# 2126_B_MatrixBoard_AffichageMatricielNom.net
KiCad netlist of a schematic drawn in Altium Designer
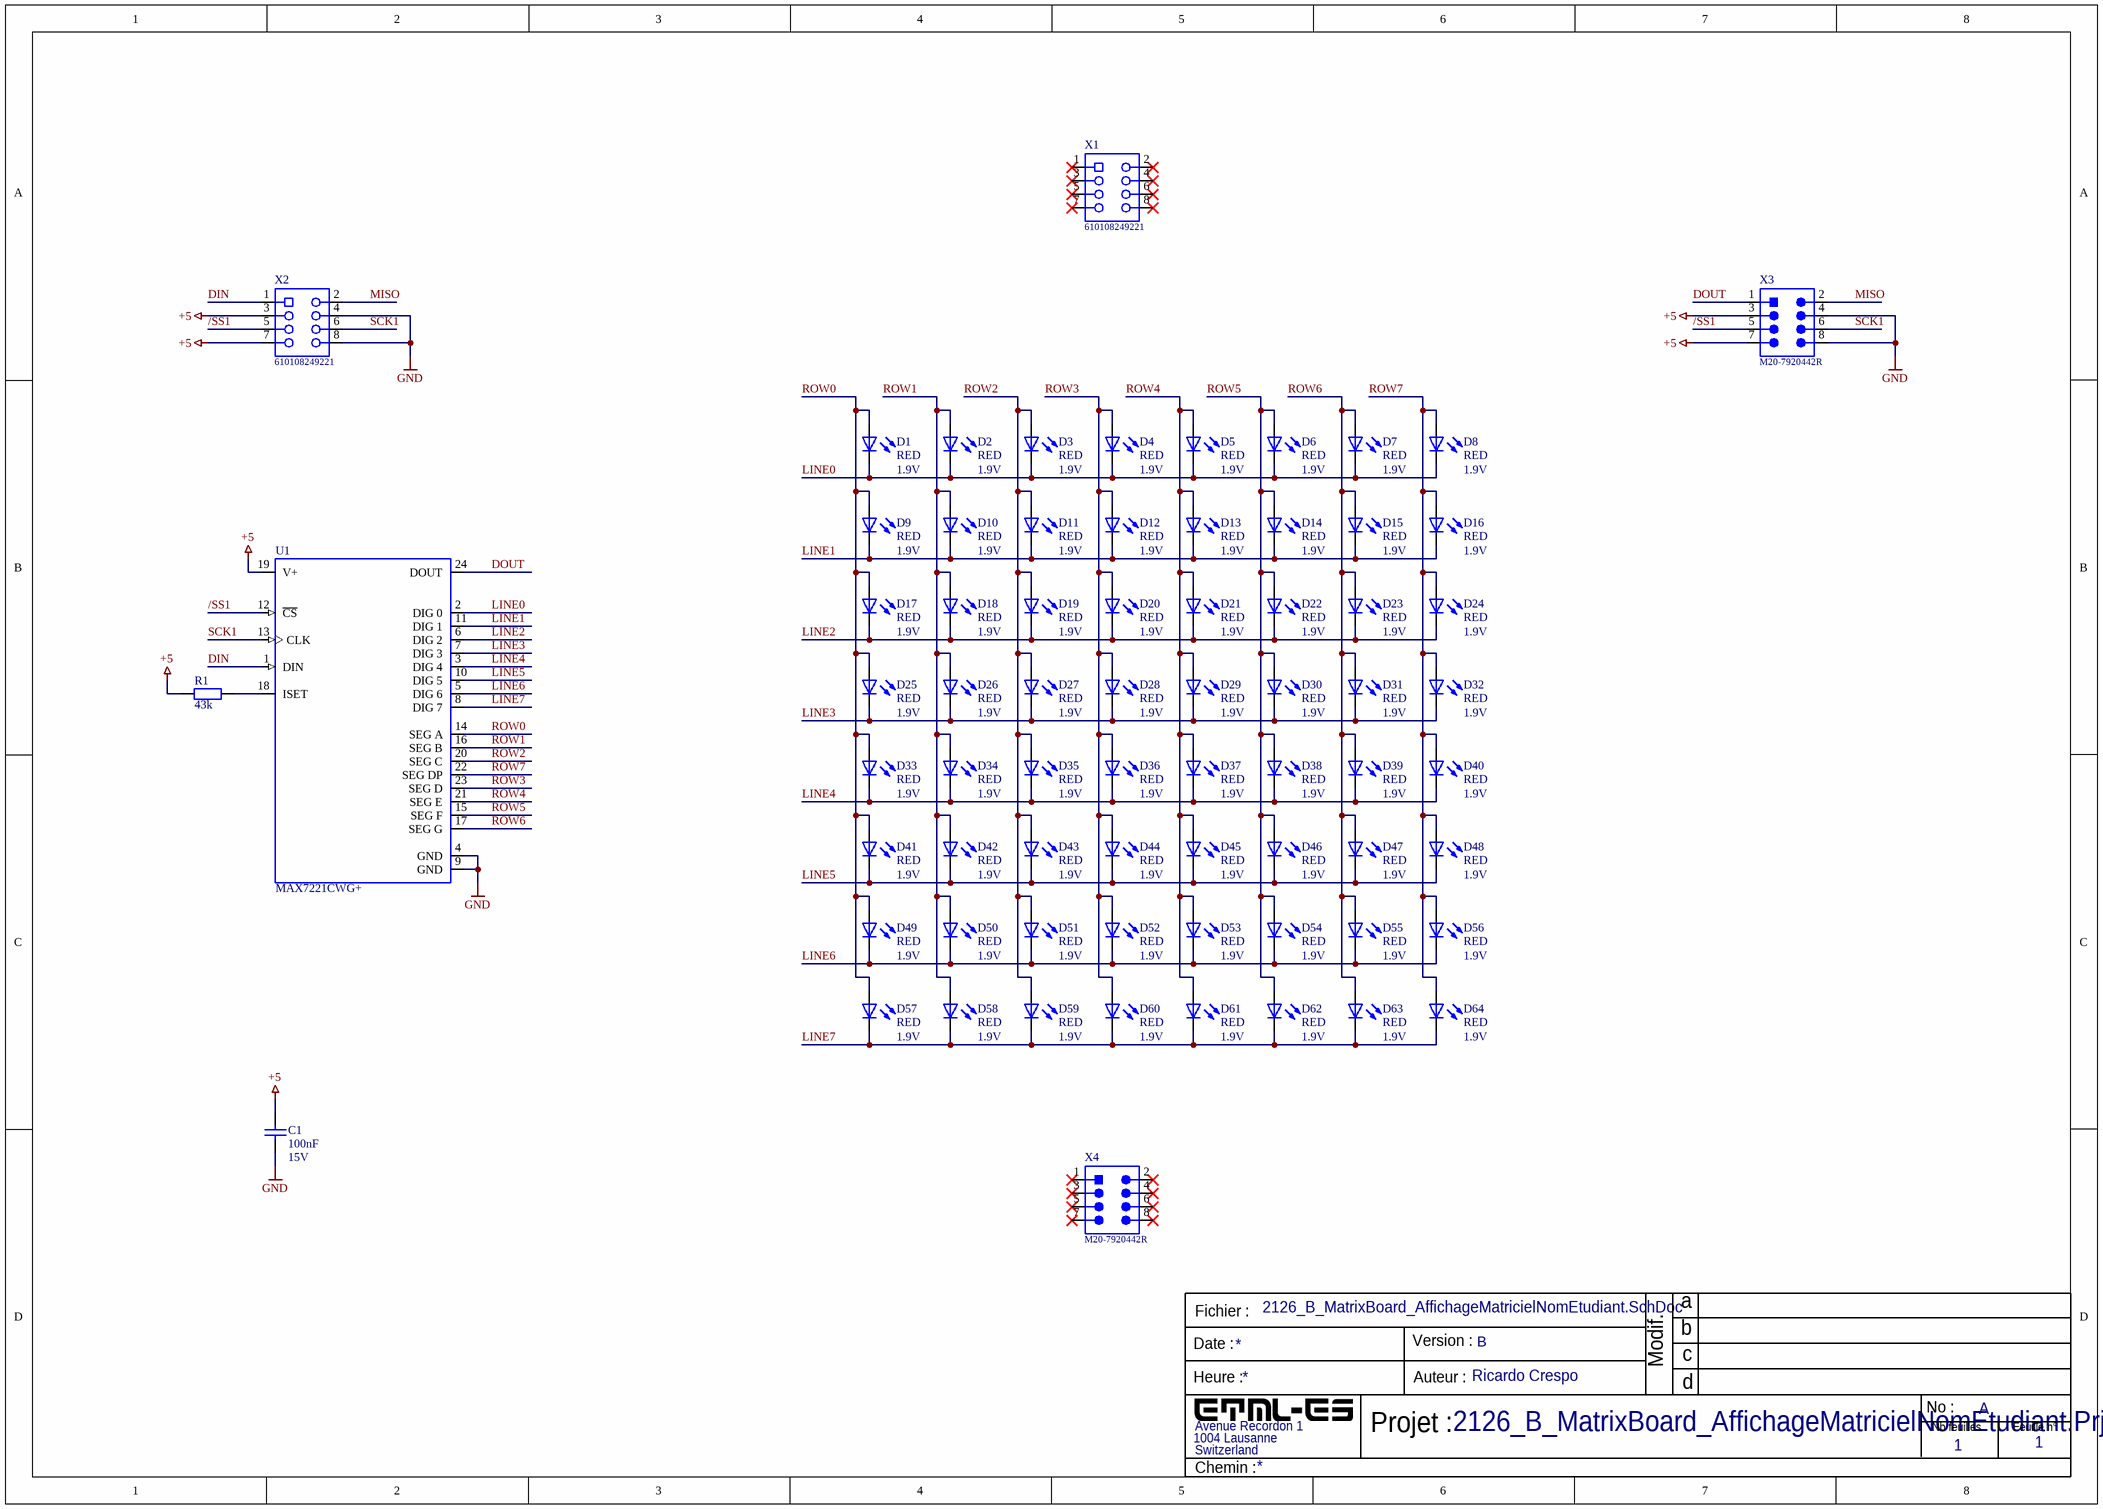
[diagram p0: 2126_B_MatrixBoard_AffichageMatricielNomEtudiant.SchDoc]

(export (version "E")
  (design (tool "Eeschema 10.0.6"))
  (components
    (comp (ref "C1")
      (value "100nF")
      (footprint "CAPC2013X145X48NL20T23")
      (description "VJ0805Y104KNAAT")
      (fields (field (name "MANUFACTURER") "Vitramon"))
      (libsource (lib "2126_AffichageMatriciel") (part "CMP-2007-03167-1"))
    )
    (comp (ref "D1")
      (value "RED")
      (footprint "SODFL350X210-2N")
      (description "WL-TMRC THT Mono-color Round Color, size 3mm, Bright Green, 2.1V, 40deg")
      (fields (field (name "PART NUMBER") "151031VS04000") (field (name "PUBLISHER") "Wurth Elektronik"))
      (libsource (lib "2126_AffichageMatriciel") (part "151031VS04000"))
    )
    (comp (ref "D2")
      (value "RED")
      (footprint "SODFL350X210-2N")
      (description "WL-TMRC THT Mono-color Round Color, size 3mm, Bright Green, 2.1V, 40deg")
      (fields (field (name "PART NUMBER") "151031VS04000") (field (name "PUBLISHER") "Wurth Elektronik"))
      (libsource (lib "2126_AffichageMatriciel") (part "151031VS04000"))
    )
    (comp (ref "D3")
      (value "RED")
      (footprint "SODFL350X210-2N")
      (description "WL-TMRC THT Mono-color Round Color, size 3mm, Bright Green, 2.1V, 40deg")
      (fields (field (name "PART NUMBER") "151031VS04000") (field (name "PUBLISHER") "Wurth Elektronik"))
      (libsource (lib "2126_AffichageMatriciel") (part "151031VS04000"))
    )
    (comp (ref "D4")
      (value "RED")
      (footprint "SODFL350X210-2N")
      (description "WL-TMRC THT Mono-color Round Color, size 3mm, Bright Green, 2.1V, 40deg")
      (fields (field (name "PART NUMBER") "151031VS04000") (field (name "PUBLISHER") "Wurth Elektronik"))
      (libsource (lib "2126_AffichageMatriciel") (part "151031VS04000"))
    )
    (comp (ref "D5")
      (value "RED")
      (footprint "SODFL350X210-2N")
      (description "WL-TMRC THT Mono-color Round Color, size 3mm, Bright Green, 2.1V, 40deg")
      (fields (field (name "PART NUMBER") "151031VS04000") (field (name "PUBLISHER") "Wurth Elektronik"))
      (libsource (lib "2126_AffichageMatriciel") (part "151031VS04000"))
    )
    (comp (ref "D6")
      (value "RED")
      (footprint "SODFL350X210-2N")
      (description "WL-TMRC THT Mono-color Round Color, size 3mm, Bright Green, 2.1V, 40deg")
      (fields (field (name "PART NUMBER") "151031VS04000") (field (name "PUBLISHER") "Wurth Elektronik"))
      (libsource (lib "2126_AffichageMatriciel") (part "151031VS04000"))
    )
    (comp (ref "D7")
      (value "RED")
      (footprint "SODFL350X210-2N")
      (description "WL-TMRC THT Mono-color Round Color, size 3mm, Bright Green, 2.1V, 40deg")
      (fields (field (name "PART NUMBER") "151031VS04000") (field (name "PUBLISHER") "Wurth Elektronik"))
      (libsource (lib "2126_AffichageMatriciel") (part "151031VS04000"))
    )
    (comp (ref "D8")
      (value "RED")
      (footprint "SODFL350X210-2N")
      (description "WL-TMRC THT Mono-color Round Color, size 3mm, Bright Green, 2.1V, 40deg")
      (fields (field (name "PART NUMBER") "151031VS04000") (field (name "PUBLISHER") "Wurth Elektronik"))
      (libsource (lib "2126_AffichageMatriciel") (part "151031VS04000"))
    )
    (comp (ref "D9")
      (value "RED")
      (footprint "SODFL350X210-2N")
      (description "WL-TMRC THT Mono-color Round Color, size 3mm, Bright Green, 2.1V, 40deg")
      (fields (field (name "PART NUMBER") "151031VS04000") (field (name "PUBLISHER") "Wurth Elektronik"))
      (libsource (lib "2126_AffichageMatriciel") (part "151031VS04000"))
    )
    (comp (ref "D10")
      (value "RED")
      (footprint "SODFL350X210-2N")
      (description "WL-TMRC THT Mono-color Round Color, size 3mm, Bright Green, 2.1V, 40deg")
      (fields (field (name "PART NUMBER") "151031VS04000") (field (name "PUBLISHER") "Wurth Elektronik"))
      (libsource (lib "2126_AffichageMatriciel") (part "151031VS04000"))
    )
    (comp (ref "D11")
      (value "RED")
      (footprint "SODFL350X210-2N")
      (description "WL-TMRC THT Mono-color Round Color, size 3mm, Bright Green, 2.1V, 40deg")
      (fields (field (name "PART NUMBER") "151031VS04000") (field (name "PUBLISHER") "Wurth Elektronik"))
      (libsource (lib "2126_AffichageMatriciel") (part "151031VS04000"))
    )
    (comp (ref "D12")
      (value "RED")
      (footprint "SODFL350X210-2N")
      (description "WL-TMRC THT Mono-color Round Color, size 3mm, Bright Green, 2.1V, 40deg")
      (fields (field (name "PART NUMBER") "151031VS04000") (field (name "PUBLISHER") "Wurth Elektronik"))
      (libsource (lib "2126_AffichageMatriciel") (part "151031VS04000"))
    )
    (comp (ref "D13")
      (value "RED")
      (footprint "SODFL350X210-2N")
      (description "WL-TMRC THT Mono-color Round Color, size 3mm, Bright Green, 2.1V, 40deg")
      (fields (field (name "PART NUMBER") "151031VS04000") (field (name "PUBLISHER") "Wurth Elektronik"))
      (libsource (lib "2126_AffichageMatriciel") (part "151031VS04000"))
    )
    (comp (ref "D14")
      (value "RED")
      (footprint "SODFL350X210-2N")
      (description "WL-TMRC THT Mono-color Round Color, size 3mm, Bright Green, 2.1V, 40deg")
      (fields (field (name "PART NUMBER") "151031VS04000") (field (name "PUBLISHER") "Wurth Elektronik"))
      (libsource (lib "2126_AffichageMatriciel") (part "151031VS04000"))
    )
    (comp (ref "D15")
      (value "RED")
      (footprint "SODFL350X210-2N")
      (description "WL-TMRC THT Mono-color Round Color, size 3mm, Bright Green, 2.1V, 40deg")
      (fields (field (name "PART NUMBER") "151031VS04000") (field (name "PUBLISHER") "Wurth Elektronik"))
      (libsource (lib "2126_AffichageMatriciel") (part "151031VS04000"))
    )
    (comp (ref "D16")
      (value "RED")
      (footprint "SODFL350X210-2N")
      (description "WL-TMRC THT Mono-color Round Color, size 3mm, Bright Green, 2.1V, 40deg")
      (fields (field (name "PART NUMBER") "151031VS04000") (field (name "PUBLISHER") "Wurth Elektronik"))
      (libsource (lib "2126_AffichageMatriciel") (part "151031VS04000"))
    )
    (comp (ref "D17")
      (value "RED")
      (footprint "SODFL350X210-2N")
      (description "WL-TMRC THT Mono-color Round Color, size 3mm, Bright Green, 2.1V, 40deg")
      (fields (field (name "PART NUMBER") "151031VS04000") (field (name "PUBLISHER") "Wurth Elektronik"))
      (libsource (lib "2126_AffichageMatriciel") (part "151031VS04000"))
    )
    (comp (ref "D18")
      (value "RED")
      (footprint "SODFL350X210-2N")
      (description "WL-TMRC THT Mono-color Round Color, size 3mm, Bright Green, 2.1V, 40deg")
      (fields (field (name "PART NUMBER") "151031VS04000") (field (name "PUBLISHER") "Wurth Elektronik"))
      (libsource (lib "2126_AffichageMatriciel") (part "151031VS04000"))
    )
    (comp (ref "D19")
      (value "RED")
      (footprint "SODFL350X210-2N")
      (description "WL-TMRC THT Mono-color Round Color, size 3mm, Bright Green, 2.1V, 40deg")
      (fields (field (name "PART NUMBER") "151031VS04000") (field (name "PUBLISHER") "Wurth Elektronik"))
      (libsource (lib "2126_AffichageMatriciel") (part "151031VS04000"))
    )
    (comp (ref "D20")
      (value "RED")
      (footprint "SODFL350X210-2N")
      (description "WL-TMRC THT Mono-color Round Color, size 3mm, Bright Green, 2.1V, 40deg")
      (fields (field (name "PART NUMBER") "151031VS04000") (field (name "PUBLISHER") "Wurth Elektronik"))
      (libsource (lib "2126_AffichageMatriciel") (part "151031VS04000"))
    )
    (comp (ref "D21")
      (value "RED")
      (footprint "SODFL350X210-2N")
      (description "WL-TMRC THT Mono-color Round Color, size 3mm, Bright Green, 2.1V, 40deg")
      (fields (field (name "PART NUMBER") "151031VS04000") (field (name "PUBLISHER") "Wurth Elektronik"))
      (libsource (lib "2126_AffichageMatriciel") (part "151031VS04000"))
    )
    (comp (ref "D22")
      (value "RED")
      (footprint "SODFL350X210-2N")
      (description "WL-TMRC THT Mono-color Round Color, size 3mm, Bright Green, 2.1V, 40deg")
      (fields (field (name "PART NUMBER") "151031VS04000") (field (name "PUBLISHER") "Wurth Elektronik"))
      (libsource (lib "2126_AffichageMatriciel") (part "151031VS04000"))
    )
    (comp (ref "D23")
      (value "RED")
      (footprint "SODFL350X210-2N")
      (description "WL-TMRC THT Mono-color Round Color, size 3mm, Bright Green, 2.1V, 40deg")
      (fields (field (name "PART NUMBER") "151031VS04000") (field (name "PUBLISHER") "Wurth Elektronik"))
      (libsource (lib "2126_AffichageMatriciel") (part "151031VS04000"))
    )
    (comp (ref "D24")
      (value "RED")
      (footprint "SODFL350X210-2N")
      (description "WL-TMRC THT Mono-color Round Color, size 3mm, Bright Green, 2.1V, 40deg")
      (fields (field (name "PART NUMBER") "151031VS04000") (field (name "PUBLISHER") "Wurth Elektronik"))
      (libsource (lib "2126_AffichageMatriciel") (part "151031VS04000"))
    )
    (comp (ref "D25")
      (value "RED")
      (footprint "SODFL350X210-2N")
      (description "WL-TMRC THT Mono-color Round Color, size 3mm, Bright Green, 2.1V, 40deg")
      (fields (field (name "PART NUMBER") "151031VS04000") (field (name "PUBLISHER") "Wurth Elektronik"))
      (libsource (lib "2126_AffichageMatriciel") (part "151031VS04000"))
    )
    (comp (ref "D26")
      (value "RED")
      (footprint "SODFL350X210-2N")
      (description "WL-TMRC THT Mono-color Round Color, size 3mm, Bright Green, 2.1V, 40deg")
      (fields (field (name "PART NUMBER") "151031VS04000") (field (name "PUBLISHER") "Wurth Elektronik"))
      (libsource (lib "2126_AffichageMatriciel") (part "151031VS04000"))
    )
    (comp (ref "D27")
      (value "RED")
      (footprint "SODFL350X210-2N")
      (description "WL-TMRC THT Mono-color Round Color, size 3mm, Bright Green, 2.1V, 40deg")
      (fields (field (name "PART NUMBER") "151031VS04000") (field (name "PUBLISHER") "Wurth Elektronik"))
      (libsource (lib "2126_AffichageMatriciel") (part "151031VS04000"))
    )
    (comp (ref "D28")
      (value "RED")
      (footprint "SODFL350X210-2N")
      (description "WL-TMRC THT Mono-color Round Color, size 3mm, Bright Green, 2.1V, 40deg")
      (fields (field (name "PART NUMBER") "151031VS04000") (field (name "PUBLISHER") "Wurth Elektronik"))
      (libsource (lib "2126_AffichageMatriciel") (part "151031VS04000"))
    )
    (comp (ref "D29")
      (value "RED")
      (footprint "SODFL350X210-2N")
      (description "WL-TMRC THT Mono-color Round Color, size 3mm, Bright Green, 2.1V, 40deg")
      (fields (field (name "PART NUMBER") "151031VS04000") (field (name "PUBLISHER") "Wurth Elektronik"))
      (libsource (lib "2126_AffichageMatriciel") (part "151031VS04000"))
    )
    (comp (ref "D30")
      (value "RED")
      (footprint "SODFL350X210-2N")
      (description "WL-TMRC THT Mono-color Round Color, size 3mm, Bright Green, 2.1V, 40deg")
      (fields (field (name "PART NUMBER") "151031VS04000") (field (name "PUBLISHER") "Wurth Elektronik"))
      (libsource (lib "2126_AffichageMatriciel") (part "151031VS04000"))
    )
    (comp (ref "D31")
      (value "RED")
      (footprint "SODFL350X210-2N")
      (description "WL-TMRC THT Mono-color Round Color, size 3mm, Bright Green, 2.1V, 40deg")
      (fields (field (name "PART NUMBER") "151031VS04000") (field (name "PUBLISHER") "Wurth Elektronik"))
      (libsource (lib "2126_AffichageMatriciel") (part "151031VS04000"))
    )
    (comp (ref "D32")
      (value "RED")
      (footprint "SODFL350X210-2N")
      (description "WL-TMRC THT Mono-color Round Color, size 3mm, Bright Green, 2.1V, 40deg")
      (fields (field (name "PART NUMBER") "151031VS04000") (field (name "PUBLISHER") "Wurth Elektronik"))
      (libsource (lib "2126_AffichageMatriciel") (part "151031VS04000"))
    )
    (comp (ref "D33")
      (value "RED")
      (footprint "SODFL350X210-2N")
      (description "WL-TMRC THT Mono-color Round Color, size 3mm, Bright Green, 2.1V, 40deg")
      (fields (field (name "PART NUMBER") "151031VS04000") (field (name "PUBLISHER") "Wurth Elektronik"))
      (libsource (lib "2126_AffichageMatriciel") (part "151031VS04000"))
    )
    (comp (ref "D34")
      (value "RED")
      (footprint "SODFL350X210-2N")
      (description "WL-TMRC THT Mono-color Round Color, size 3mm, Bright Green, 2.1V, 40deg")
      (fields (field (name "PART NUMBER") "151031VS04000") (field (name "PUBLISHER") "Wurth Elektronik"))
      (libsource (lib "2126_AffichageMatriciel") (part "151031VS04000"))
    )
    (comp (ref "D35")
      (value "RED")
      (footprint "SODFL350X210-2N")
      (description "WL-TMRC THT Mono-color Round Color, size 3mm, Bright Green, 2.1V, 40deg")
      (fields (field (name "PART NUMBER") "151031VS04000") (field (name "PUBLISHER") "Wurth Elektronik"))
      (libsource (lib "2126_AffichageMatriciel") (part "151031VS04000"))
    )
    (comp (ref "D36")
      (value "RED")
      (footprint "SODFL350X210-2N")
      (description "WL-TMRC THT Mono-color Round Color, size 3mm, Bright Green, 2.1V, 40deg")
      (fields (field (name "PART NUMBER") "151031VS04000") (field (name "PUBLISHER") "Wurth Elektronik"))
      (libsource (lib "2126_AffichageMatriciel") (part "151031VS04000"))
    )
    (comp (ref "D37")
      (value "RED")
      (footprint "SODFL350X210-2N")
      (description "WL-TMRC THT Mono-color Round Color, size 3mm, Bright Green, 2.1V, 40deg")
      (fields (field (name "PART NUMBER") "151031VS04000") (field (name "PUBLISHER") "Wurth Elektronik"))
      (libsource (lib "2126_AffichageMatriciel") (part "151031VS04000"))
    )
    (comp (ref "D38")
      (value "RED")
      (footprint "SODFL350X210-2N")
      (description "WL-TMRC THT Mono-color Round Color, size 3mm, Bright Green, 2.1V, 40deg")
      (fields (field (name "PART NUMBER") "151031VS04000") (field (name "PUBLISHER") "Wurth Elektronik"))
      (libsource (lib "2126_AffichageMatriciel") (part "151031VS04000"))
    )
    (comp (ref "D39")
      (value "RED")
      (footprint "SODFL350X210-2N")
      (description "WL-TMRC THT Mono-color Round Color, size 3mm, Bright Green, 2.1V, 40deg")
      (fields (field (name "PART NUMBER") "151031VS04000") (field (name "PUBLISHER") "Wurth Elektronik"))
      (libsource (lib "2126_AffichageMatriciel") (part "151031VS04000"))
    )
    (comp (ref "D40")
      (value "RED")
      (footprint "SODFL350X210-2N")
      (description "WL-TMRC THT Mono-color Round Color, size 3mm, Bright Green, 2.1V, 40deg")
      (fields (field (name "PART NUMBER") "151031VS04000") (field (name "PUBLISHER") "Wurth Elektronik"))
      (libsource (lib "2126_AffichageMatriciel") (part "151031VS04000"))
    )
    (comp (ref "D41")
      (value "RED")
      (footprint "SODFL350X210-2N")
      (description "WL-TMRC THT Mono-color Round Color, size 3mm, Bright Green, 2.1V, 40deg")
      (fields (field (name "PART NUMBER") "151031VS04000") (field (name "PUBLISHER") "Wurth Elektronik"))
      (libsource (lib "2126_AffichageMatriciel") (part "151031VS04000"))
    )
    (comp (ref "D42")
      (value "RED")
      (footprint "SODFL350X210-2N")
      (description "WL-TMRC THT Mono-color Round Color, size 3mm, Bright Green, 2.1V, 40deg")
      (fields (field (name "PART NUMBER") "151031VS04000") (field (name "PUBLISHER") "Wurth Elektronik"))
      (libsource (lib "2126_AffichageMatriciel") (part "151031VS04000"))
    )
    (comp (ref "D43")
      (value "RED")
      (footprint "SODFL350X210-2N")
      (description "WL-TMRC THT Mono-color Round Color, size 3mm, Bright Green, 2.1V, 40deg")
      (fields (field (name "PART NUMBER") "151031VS04000") (field (name "PUBLISHER") "Wurth Elektronik"))
      (libsource (lib "2126_AffichageMatriciel") (part "151031VS04000"))
    )
    (comp (ref "D44")
      (value "RED")
      (footprint "SODFL350X210-2N")
      (description "WL-TMRC THT Mono-color Round Color, size 3mm, Bright Green, 2.1V, 40deg")
      (fields (field (name "PART NUMBER") "151031VS04000") (field (name "PUBLISHER") "Wurth Elektronik"))
      (libsource (lib "2126_AffichageMatriciel") (part "151031VS04000"))
    )
    (comp (ref "D45")
      (value "RED")
      (footprint "SODFL350X210-2N")
      (description "WL-TMRC THT Mono-color Round Color, size 3mm, Bright Green, 2.1V, 40deg")
      (fields (field (name "PART NUMBER") "151031VS04000") (field (name "PUBLISHER") "Wurth Elektronik"))
      (libsource (lib "2126_AffichageMatriciel") (part "151031VS04000"))
    )
    (comp (ref "D46")
      (value "RED")
      (footprint "SODFL350X210-2N")
      (description "WL-TMRC THT Mono-color Round Color, size 3mm, Bright Green, 2.1V, 40deg")
      (fields (field (name "PART NUMBER") "151031VS04000") (field (name "PUBLISHER") "Wurth Elektronik"))
      (libsource (lib "2126_AffichageMatriciel") (part "151031VS04000"))
    )
    (comp (ref "D47")
      (value "RED")
      (footprint "SODFL350X210-2N")
      (description "WL-TMRC THT Mono-color Round Color, size 3mm, Bright Green, 2.1V, 40deg")
      (fields (field (name "PART NUMBER") "151031VS04000") (field (name "PUBLISHER") "Wurth Elektronik"))
      (libsource (lib "2126_AffichageMatriciel") (part "151031VS04000"))
    )
    (comp (ref "D48")
      (value "RED")
      (footprint "SODFL350X210-2N")
      (description "WL-TMRC THT Mono-color Round Color, size 3mm, Bright Green, 2.1V, 40deg")
      (fields (field (name "PART NUMBER") "151031VS04000") (field (name "PUBLISHER") "Wurth Elektronik"))
      (libsource (lib "2126_AffichageMatriciel") (part "151031VS04000"))
    )
    (comp (ref "D49")
      (value "RED")
      (footprint "SODFL350X210-2N")
      (description "WL-TMRC THT Mono-color Round Color, size 3mm, Bright Green, 2.1V, 40deg")
      (fields (field (name "PART NUMBER") "151031VS04000") (field (name "PUBLISHER") "Wurth Elektronik"))
      (libsource (lib "2126_AffichageMatriciel") (part "151031VS04000"))
    )
    (comp (ref "D50")
      (value "RED")
      (footprint "SODFL350X210-2N")
      (description "WL-TMRC THT Mono-color Round Color, size 3mm, Bright Green, 2.1V, 40deg")
      (fields (field (name "PART NUMBER") "151031VS04000") (field (name "PUBLISHER") "Wurth Elektronik"))
      (libsource (lib "2126_AffichageMatriciel") (part "151031VS04000"))
    )
    (comp (ref "D51")
      (value "RED")
      (footprint "SODFL350X210-2N")
      (description "WL-TMRC THT Mono-color Round Color, size 3mm, Bright Green, 2.1V, 40deg")
      (fields (field (name "PART NUMBER") "151031VS04000") (field (name "PUBLISHER") "Wurth Elektronik"))
      (libsource (lib "2126_AffichageMatriciel") (part "151031VS04000"))
    )
    (comp (ref "D52")
      (value "RED")
      (footprint "SODFL350X210-2N")
      (description "WL-TMRC THT Mono-color Round Color, size 3mm, Bright Green, 2.1V, 40deg")
      (fields (field (name "PART NUMBER") "151031VS04000") (field (name "PUBLISHER") "Wurth Elektronik"))
      (libsource (lib "2126_AffichageMatriciel") (part "151031VS04000"))
    )
    (comp (ref "D53")
      (value "RED")
      (footprint "SODFL350X210-2N")
      (description "WL-TMRC THT Mono-color Round Color, size 3mm, Bright Green, 2.1V, 40deg")
      (fields (field (name "PART NUMBER") "151031VS04000") (field (name "PUBLISHER") "Wurth Elektronik"))
      (libsource (lib "2126_AffichageMatriciel") (part "151031VS04000"))
    )
    (comp (ref "D54")
      (value "RED")
      (footprint "SODFL350X210-2N")
      (description "WL-TMRC THT Mono-color Round Color, size 3mm, Bright Green, 2.1V, 40deg")
      (fields (field (name "PART NUMBER") "151031VS04000") (field (name "PUBLISHER") "Wurth Elektronik"))
      (libsource (lib "2126_AffichageMatriciel") (part "151031VS04000"))
    )
    (comp (ref "D55")
      (value "RED")
      (footprint "SODFL350X210-2N")
      (description "WL-TMRC THT Mono-color Round Color, size 3mm, Bright Green, 2.1V, 40deg")
      (fields (field (name "PART NUMBER") "151031VS04000") (field (name "PUBLISHER") "Wurth Elektronik"))
      (libsource (lib "2126_AffichageMatriciel") (part "151031VS04000"))
    )
    (comp (ref "D56")
      (value "RED")
      (footprint "SODFL350X210-2N")
      (description "WL-TMRC THT Mono-color Round Color, size 3mm, Bright Green, 2.1V, 40deg")
      (fields (field (name "PART NUMBER") "151031VS04000") (field (name "PUBLISHER") "Wurth Elektronik"))
      (libsource (lib "2126_AffichageMatriciel") (part "151031VS04000"))
    )
    (comp (ref "D57")
      (value "RED")
      (footprint "SODFL350X210-2N")
      (description "WL-TMRC THT Mono-color Round Color, size 3mm, Bright Green, 2.1V, 40deg")
      (fields (field (name "PART NUMBER") "151031VS04000") (field (name "PUBLISHER") "Wurth Elektronik"))
      (libsource (lib "2126_AffichageMatriciel") (part "151031VS04000"))
    )
    (comp (ref "D58")
      (value "RED")
      (footprint "SODFL350X210-2N")
      (description "WL-TMRC THT Mono-color Round Color, size 3mm, Bright Green, 2.1V, 40deg")
      (fields (field (name "PART NUMBER") "151031VS04000") (field (name "PUBLISHER") "Wurth Elektronik"))
      (libsource (lib "2126_AffichageMatriciel") (part "151031VS04000"))
    )
    (comp (ref "D59")
      (value "RED")
      (footprint "SODFL350X210-2N")
      (description "WL-TMRC THT Mono-color Round Color, size 3mm, Bright Green, 2.1V, 40deg")
      (fields (field (name "PART NUMBER") "151031VS04000") (field (name "PUBLISHER") "Wurth Elektronik"))
      (libsource (lib "2126_AffichageMatriciel") (part "151031VS04000"))
    )
    (comp (ref "D60")
      (value "RED")
      (footprint "SODFL350X210-2N")
      (description "WL-TMRC THT Mono-color Round Color, size 3mm, Bright Green, 2.1V, 40deg")
      (fields (field (name "PART NUMBER") "151031VS04000") (field (name "PUBLISHER") "Wurth Elektronik"))
      (libsource (lib "2126_AffichageMatriciel") (part "151031VS04000"))
    )
    (comp (ref "D61")
      (value "RED")
      (footprint "SODFL350X210-2N")
      (description "WL-TMRC THT Mono-color Round Color, size 3mm, Bright Green, 2.1V, 40deg")
      (fields (field (name "PART NUMBER") "151031VS04000") (field (name "PUBLISHER") "Wurth Elektronik"))
      (libsource (lib "2126_AffichageMatriciel") (part "151031VS04000"))
    )
    (comp (ref "D62")
      (value "RED")
      (footprint "SODFL350X210-2N")
      (description "WL-TMRC THT Mono-color Round Color, size 3mm, Bright Green, 2.1V, 40deg")
      (fields (field (name "PART NUMBER") "151031VS04000") (field (name "PUBLISHER") "Wurth Elektronik"))
      (libsource (lib "2126_AffichageMatriciel") (part "151031VS04000"))
    )
    (comp (ref "D63")
      (value "RED")
      (footprint "SODFL350X210-2N")
      (description "WL-TMRC THT Mono-color Round Color, size 3mm, Bright Green, 2.1V, 40deg")
      (fields (field (name "PART NUMBER") "151031VS04000") (field (name "PUBLISHER") "Wurth Elektronik"))
      (libsource (lib "2126_AffichageMatriciel") (part "151031VS04000"))
    )
    (comp (ref "D64")
      (value "RED")
      (footprint "SODFL350X210-2N")
      (description "WL-TMRC THT Mono-color Round Color, size 3mm, Bright Green, 2.1V, 40deg")
      (fields (field (name "PART NUMBER") "151031VS04000") (field (name "PUBLISHER") "Wurth Elektronik"))
      (libsource (lib "2126_AffichageMatriciel") (part "151031VS04000"))
    )
    (comp (ref "R1")
      (value "43k")
      (footprint "RESC2013X70X40ML20T20")
      (description "10K 0.125W 1% 0805 (2012 Metric)  SMD")
      (fields (field (name "TOLERANCE") "1 %") (field (name "POWER") "0.125 W"))
      (libsource (lib "2126_AffichageMatriciel") (part "CMP-1013-00623-1"))
    )
    (comp (ref "U1")
      (value "MAX7221CWG+")
      (footprint "FP-W24-1-IPC_B")
      (description "IC DRVR 7 SEGMNT 8 DIGIT 24SOIC")
      (fields
        (field (name "MANUFACTURER") "Maxim Integrated")
        (field (name "OCTOPART") "https://octopart.com/max7221cwg%2B-maxim+integrated-39581478")
      )
      (libsource (lib "2126_AffichageMatriciel") (part "CMP-05718-000002-1"))
    )
    (comp (ref "X1")
      (value "610108249221")
      (footprint "610108249221")
      (description "WR-PHD Socket Header, THT, pitch 2.54mm, Dual Row, Angled, 8p")
      (fields
        (field (name "MANUFACTURER PART NUMBER") "613008243121")
        (field (name "MANUFACTURER") "Wurth Elektronik")
      )
      (libsource (lib "2126_AffichageMatriciel") (part "610108249221"))
    )
    (comp (ref "X2")
      (value "610108249221")
      (footprint "610108249221")
      (description "WR-PHD Socket Header, THT, pitch 2.54mm, Dual Row, Angled, 8p")
      (fields
        (field (name "MANUFACTURER PART NUMBER") "613008243121")
        (field (name "MANUFACTURER") "Wurth Elektronik")
      )
      (libsource (lib "2126_AffichageMatriciel") (part "610108249221"))
    )
    (comp (ref "X3")
      (value "M20-7920442R")
      (footprint "610108249121")
      (description "WR-PHD Pin Header, THT, pitch 2.54mm, Dual Row, Angled, 8p")
      (fields
        (field (name "MANUFACTURER PART NUMBER") "61300821021")
        (field (name "MANUFACTURER") "Wurth Elektronik")
      )
      (libsource (lib "2126_AffichageMatriciel") (part "610108249121"))
    )
    (comp (ref "X4")
      (value "M20-7920442R")
      (footprint "610108249121")
      (description "WR-PHD Pin Header, THT, pitch 2.54mm, Dual Row, Angled, 8p")
      (fields
        (field (name "MANUFACTURER PART NUMBER") "61300821021")
        (field (name "MANUFACTURER") "Wurth Elektronik")
      )
      (libsource (lib "2126_AffichageMatriciel") (part "610108249121"))
    )
  )
  (nets
    (net (code "1") (name "+5") (class "Default")
      (node (ref "C1") (pin "2") (pinfunction "2_2") (pintype "passive"))
      (node (ref "R1") (pin "1") (pinfunction "1_1") (pintype "passive"))
      (node (ref "U1") (pin "19") (pinfunction "V+_19") (pintype "power_in"))
      (node (ref "X2") (pin "3") (pinfunction "3_3") (pintype "passive"))
      (node (ref "X2") (pin "7") (pinfunction "7_7") (pintype "passive"))
      (node (ref "X3") (pin "3") (pinfunction "3_3") (pintype "passive"))
      (node (ref "X3") (pin "7") (pinfunction "7_7") (pintype "passive"))
    )
    (net (code "2") (name "/DIN") (class "Default")
      (node (ref "U1") (pin "1") (pinfunction "DIN_1") (pintype "input"))
      (node (ref "X2") (pin "1") (pinfunction "1_1") (pintype "passive"))
    )
    (net (code "3") (name "/DOUT") (class "Default")
      (node (ref "U1") (pin "24") (pinfunction "DOUT_24") (pintype "passive"))
      (node (ref "X3") (pin "1") (pinfunction "1_1") (pintype "passive"))
    )
    (net (code "4") (name "/LINE0") (class "Default")
      (node (ref "D1") (pin "K") (pinfunction "K_K") (pintype "passive"))
      (node (ref "D2") (pin "K") (pinfunction "K_K") (pintype "passive"))
      (node (ref "D3") (pin "K") (pinfunction "K_K") (pintype "passive"))
      (node (ref "D4") (pin "K") (pinfunction "K_K") (pintype "passive"))
      (node (ref "D5") (pin "K") (pinfunction "K_K") (pintype "passive"))
      (node (ref "D6") (pin "K") (pinfunction "K_K") (pintype "passive"))
      (node (ref "D7") (pin "K") (pinfunction "K_K") (pintype "passive"))
      (node (ref "D8") (pin "K") (pinfunction "K_K") (pintype "passive"))
      (node (ref "U1") (pin "2") (pinfunction "DIG_0_2") (pintype "passive"))
    )
    (net (code "5") (name "/LINE1") (class "Default")
      (node (ref "D10") (pin "K") (pinfunction "K_K") (pintype "passive"))
      (node (ref "D11") (pin "K") (pinfunction "K_K") (pintype "passive"))
      (node (ref "D12") (pin "K") (pinfunction "K_K") (pintype "passive"))
      (node (ref "D13") (pin "K") (pinfunction "K_K") (pintype "passive"))
      (node (ref "D14") (pin "K") (pinfunction "K_K") (pintype "passive"))
      (node (ref "D15") (pin "K") (pinfunction "K_K") (pintype "passive"))
      (node (ref "D16") (pin "K") (pinfunction "K_K") (pintype "passive"))
      (node (ref "D9") (pin "K") (pinfunction "K_K") (pintype "passive"))
      (node (ref "U1") (pin "11") (pinfunction "DIG_1_11") (pintype "passive"))
    )
    (net (code "6") (name "/LINE2") (class "Default")
      (node (ref "D17") (pin "K") (pinfunction "K_K") (pintype "passive"))
      (node (ref "D18") (pin "K") (pinfunction "K_K") (pintype "passive"))
      (node (ref "D19") (pin "K") (pinfunction "K_K") (pintype "passive"))
      (node (ref "D20") (pin "K") (pinfunction "K_K") (pintype "passive"))
      (node (ref "D21") (pin "K") (pinfunction "K_K") (pintype "passive"))
      (node (ref "D22") (pin "K") (pinfunction "K_K") (pintype "passive"))
      (node (ref "D23") (pin "K") (pinfunction "K_K") (pintype "passive"))
      (node (ref "D24") (pin "K") (pinfunction "K_K") (pintype "passive"))
      (node (ref "U1") (pin "6") (pinfunction "DIG_2_6") (pintype "passive"))
    )
    (net (code "7") (name "/LINE3") (class "Default")
      (node (ref "D25") (pin "K") (pinfunction "K_K") (pintype "passive"))
      (node (ref "D26") (pin "K") (pinfunction "K_K") (pintype "passive"))
      (node (ref "D27") (pin "K") (pinfunction "K_K") (pintype "passive"))
      (node (ref "D28") (pin "K") (pinfunction "K_K") (pintype "passive"))
      (node (ref "D29") (pin "K") (pinfunction "K_K") (pintype "passive"))
      (node (ref "D30") (pin "K") (pinfunction "K_K") (pintype "passive"))
      (node (ref "D31") (pin "K") (pinfunction "K_K") (pintype "passive"))
      (node (ref "D32") (pin "K") (pinfunction "K_K") (pintype "passive"))
      (node (ref "U1") (pin "7") (pinfunction "DIG_3_7") (pintype "passive"))
    )
    (net (code "8") (name "/LINE4") (class "Default")
      (node (ref "D33") (pin "K") (pinfunction "K_K") (pintype "passive"))
      (node (ref "D34") (pin "K") (pinfunction "K_K") (pintype "passive"))
      (node (ref "D35") (pin "K") (pinfunction "K_K") (pintype "passive"))
      (node (ref "D36") (pin "K") (pinfunction "K_K") (pintype "passive"))
      (node (ref "D37") (pin "K") (pinfunction "K_K") (pintype "passive"))
      (node (ref "D38") (pin "K") (pinfunction "K_K") (pintype "passive"))
      (node (ref "D39") (pin "K") (pinfunction "K_K") (pintype "passive"))
      (node (ref "D40") (pin "K") (pinfunction "K_K") (pintype "passive"))
      (node (ref "U1") (pin "3") (pinfunction "DIG_4_3") (pintype "passive"))
    )
    (net (code "9") (name "/LINE5") (class "Default")
      (node (ref "D41") (pin "K") (pinfunction "K_K") (pintype "passive"))
      (node (ref "D42") (pin "K") (pinfunction "K_K") (pintype "passive"))
      (node (ref "D43") (pin "K") (pinfunction "K_K") (pintype "passive"))
      (node (ref "D44") (pin "K") (pinfunction "K_K") (pintype "passive"))
      (node (ref "D45") (pin "K") (pinfunction "K_K") (pintype "passive"))
      (node (ref "D46") (pin "K") (pinfunction "K_K") (pintype "passive"))
      (node (ref "D47") (pin "K") (pinfunction "K_K") (pintype "passive"))
      (node (ref "D48") (pin "K") (pinfunction "K_K") (pintype "passive"))
      (node (ref "U1") (pin "10") (pinfunction "DIG_5_10") (pintype "passive"))
    )
    (net (code "10") (name "/LINE6") (class "Default")
      (node (ref "D49") (pin "K") (pinfunction "K_K") (pintype "passive"))
      (node (ref "D50") (pin "K") (pinfunction "K_K") (pintype "passive"))
      (node (ref "D51") (pin "K") (pinfunction "K_K") (pintype "passive"))
      (node (ref "D52") (pin "K") (pinfunction "K_K") (pintype "passive"))
      (node (ref "D53") (pin "K") (pinfunction "K_K") (pintype "passive"))
      (node (ref "D54") (pin "K") (pinfunction "K_K") (pintype "passive"))
      (node (ref "D55") (pin "K") (pinfunction "K_K") (pintype "passive"))
      (node (ref "D56") (pin "K") (pinfunction "K_K") (pintype "passive"))
      (node (ref "U1") (pin "5") (pinfunction "DIG_6_5") (pintype "passive"))
    )
    (net (code "11") (name "/LINE7") (class "Default")
      (node (ref "D57") (pin "K") (pinfunction "K_K") (pintype "passive"))
      (node (ref "D58") (pin "K") (pinfunction "K_K") (pintype "passive"))
      (node (ref "D59") (pin "K") (pinfunction "K_K") (pintype "passive"))
      (node (ref "D60") (pin "K") (pinfunction "K_K") (pintype "passive"))
      (node (ref "D61") (pin "K") (pinfunction "K_K") (pintype "passive"))
      (node (ref "D62") (pin "K") (pinfunction "K_K") (pintype "passive"))
      (node (ref "D63") (pin "K") (pinfunction "K_K") (pintype "passive"))
      (node (ref "D64") (pin "K") (pinfunction "K_K") (pintype "passive"))
      (node (ref "U1") (pin "8") (pinfunction "DIG_7_8") (pintype "passive"))
    )
    (net (code "12") (name "/MISO") (class "Default")
      (node (ref "X2") (pin "2") (pinfunction "2_2") (pintype "passive"))
      (node (ref "X3") (pin "2") (pinfunction "2_2") (pintype "passive"))
    )
    (net (code "13") (name "/ROW0") (class "Default")
      (node (ref "D1") (pin "A") (pinfunction "A_A") (pintype "passive"))
      (node (ref "D17") (pin "A") (pinfunction "A_A") (pintype "passive"))
      (node (ref "D25") (pin "A") (pinfunction "A_A") (pintype "passive"))
      (node (ref "D33") (pin "A") (pinfunction "A_A") (pintype "passive"))
      (node (ref "D41") (pin "A") (pinfunction "A_A") (pintype "passive"))
      (node (ref "D49") (pin "A") (pinfunction "A_A") (pintype "passive"))
      (node (ref "D57") (pin "A") (pinfunction "A_A") (pintype "passive"))
      (node (ref "D9") (pin "A") (pinfunction "A_A") (pintype "passive"))
      (node (ref "U1") (pin "14") (pinfunction "SEG_A_14") (pintype "passive"))
    )
    (net (code "14") (name "/ROW1") (class "Default")
      (node (ref "D10") (pin "A") (pinfunction "A_A") (pintype "passive"))
      (node (ref "D18") (pin "A") (pinfunction "A_A") (pintype "passive"))
      (node (ref "D2") (pin "A") (pinfunction "A_A") (pintype "passive"))
      (node (ref "D26") (pin "A") (pinfunction "A_A") (pintype "passive"))
      (node (ref "D34") (pin "A") (pinfunction "A_A") (pintype "passive"))
      (node (ref "D42") (pin "A") (pinfunction "A_A") (pintype "passive"))
      (node (ref "D50") (pin "A") (pinfunction "A_A") (pintype "passive"))
      (node (ref "D58") (pin "A") (pinfunction "A_A") (pintype "passive"))
      (node (ref "U1") (pin "16") (pinfunction "SEG_B_16") (pintype "passive"))
    )
    (net (code "15") (name "/ROW2") (class "Default")
      (node (ref "D11") (pin "A") (pinfunction "A_A") (pintype "passive"))
      (node (ref "D19") (pin "A") (pinfunction "A_A") (pintype "passive"))
      (node (ref "D27") (pin "A") (pinfunction "A_A") (pintype "passive"))
      (node (ref "D3") (pin "A") (pinfunction "A_A") (pintype "passive"))
      (node (ref "D35") (pin "A") (pinfunction "A_A") (pintype "passive"))
      (node (ref "D43") (pin "A") (pinfunction "A_A") (pintype "passive"))
      (node (ref "D51") (pin "A") (pinfunction "A_A") (pintype "passive"))
      (node (ref "D59") (pin "A") (pinfunction "A_A") (pintype "passive"))
      (node (ref "U1") (pin "20") (pinfunction "SEG_C_20") (pintype "passive"))
    )
    (net (code "16") (name "/ROW3") (class "Default")
      (node (ref "D12") (pin "A") (pinfunction "A_A") (pintype "passive"))
      (node (ref "D20") (pin "A") (pinfunction "A_A") (pintype "passive"))
      (node (ref "D28") (pin "A") (pinfunction "A_A") (pintype "passive"))
      (node (ref "D36") (pin "A") (pinfunction "A_A") (pintype "passive"))
      (node (ref "D4") (pin "A") (pinfunction "A_A") (pintype "passive"))
      (node (ref "D44") (pin "A") (pinfunction "A_A") (pintype "passive"))
      (node (ref "D52") (pin "A") (pinfunction "A_A") (pintype "passive"))
      (node (ref "D60") (pin "A") (pinfunction "A_A") (pintype "passive"))
      (node (ref "U1") (pin "23") (pinfunction "SEG_D_23") (pintype "passive"))
    )
    (net (code "17") (name "/ROW4") (class "Default")
      (node (ref "D13") (pin "A") (pinfunction "A_A") (pintype "passive"))
      (node (ref "D21") (pin "A") (pinfunction "A_A") (pintype "passive"))
      (node (ref "D29") (pin "A") (pinfunction "A_A") (pintype "passive"))
      (node (ref "D37") (pin "A") (pinfunction "A_A") (pintype "passive"))
      (node (ref "D45") (pin "A") (pinfunction "A_A") (pintype "passive"))
      (node (ref "D5") (pin "A") (pinfunction "A_A") (pintype "passive"))
      (node (ref "D53") (pin "A") (pinfunction "A_A") (pintype "passive"))
      (node (ref "D61") (pin "A") (pinfunction "A_A") (pintype "passive"))
      (node (ref "U1") (pin "21") (pinfunction "SEG_E_21") (pintype "passive"))
    )
    (net (code "18") (name "/ROW5") (class "Default")
      (node (ref "D14") (pin "A") (pinfunction "A_A") (pintype "passive"))
      (node (ref "D22") (pin "A") (pinfunction "A_A") (pintype "passive"))
      (node (ref "D30") (pin "A") (pinfunction "A_A") (pintype "passive"))
      (node (ref "D38") (pin "A") (pinfunction "A_A") (pintype "passive"))
      (node (ref "D46") (pin "A") (pinfunction "A_A") (pintype "passive"))
      (node (ref "D54") (pin "A") (pinfunction "A_A") (pintype "passive"))
      (node (ref "D6") (pin "A") (pinfunction "A_A") (pintype "passive"))
      (node (ref "D62") (pin "A") (pinfunction "A_A") (pintype "passive"))
      (node (ref "U1") (pin "15") (pinfunction "SEG_F_15") (pintype "passive"))
    )
    (net (code "19") (name "/ROW6") (class "Default")
      (node (ref "D15") (pin "A") (pinfunction "A_A") (pintype "passive"))
      (node (ref "D23") (pin "A") (pinfunction "A_A") (pintype "passive"))
      (node (ref "D31") (pin "A") (pinfunction "A_A") (pintype "passive"))
      (node (ref "D39") (pin "A") (pinfunction "A_A") (pintype "passive"))
      (node (ref "D47") (pin "A") (pinfunction "A_A") (pintype "passive"))
      (node (ref "D55") (pin "A") (pinfunction "A_A") (pintype "passive"))
      (node (ref "D63") (pin "A") (pinfunction "A_A") (pintype "passive"))
      (node (ref "D7") (pin "A") (pinfunction "A_A") (pintype "passive"))
      (node (ref "U1") (pin "17") (pinfunction "SEG_G_17") (pintype "passive"))
    )
    (net (code "20") (name "/ROW7") (class "Default")
      (node (ref "D16") (pin "A") (pinfunction "A_A") (pintype "passive"))
      (node (ref "D24") (pin "A") (pinfunction "A_A") (pintype "passive"))
      (node (ref "D32") (pin "A") (pinfunction "A_A") (pintype "passive"))
      (node (ref "D40") (pin "A") (pinfunction "A_A") (pintype "passive"))
      (node (ref "D48") (pin "A") (pinfunction "A_A") (pintype "passive"))
      (node (ref "D56") (pin "A") (pinfunction "A_A") (pintype "passive"))
      (node (ref "D64") (pin "A") (pinfunction "A_A") (pintype "passive"))
      (node (ref "D8") (pin "A") (pinfunction "A_A") (pintype "passive"))
      (node (ref "U1") (pin "22") (pinfunction "SEG_DP_22") (pintype "passive"))
    )
    (net (code "21") (name "/SCK1") (class "Default")
      (node (ref "U1") (pin "13") (pinfunction "CLK_13") (pintype "input"))
      (node (ref "X2") (pin "6") (pinfunction "6_6") (pintype "passive"))
      (node (ref "X3") (pin "6") (pinfunction "6_6") (pintype "passive"))
    )
    (net (code "22") (name "/{slash}SS1") (class "Default")
      (node (ref "U1") (pin "12") (pinfunction "~{CS}_12") (pintype "input"))
      (node (ref "X2") (pin "5") (pinfunction "5_5") (pintype "passive"))
      (node (ref "X3") (pin "5") (pinfunction "5_5") (pintype "passive"))
    )
    (net (code "23") (name "GND") (class "Default")
      (node (ref "C1") (pin "1") (pinfunction "1_1") (pintype "passive"))
      (node (ref "U1") (pin "4") (pinfunction "GND_4") (pintype "power_in"))
      (node (ref "U1") (pin "9") (pinfunction "GND_9") (pintype "power_in"))
      (node (ref "X2") (pin "4") (pinfunction "4_4") (pintype "passive"))
      (node (ref "X2") (pin "8") (pinfunction "8_8") (pintype "passive"))
      (node (ref "X3") (pin "4") (pinfunction "4_4") (pintype "passive"))
      (node (ref "X3") (pin "8") (pinfunction "8_8") (pintype "passive"))
    )
    (net (code "24") (name "Net-(U1-ISET)") (class "Default")
      (node (ref "R1") (pin "2") (pinfunction "2_2") (pintype "passive"))
      (node (ref "U1") (pin "18") (pinfunction "ISET_18") (pintype "passive"))
    )
    (net (code "25") (name "unconnected-(X1-Pad1)") (class "Default")
      (node (ref "X1") (pin "1") (pinfunction "1_1") (pintype "passive+no_connect"))
    )
    (net (code "26") (name "unconnected-(X1-Pad2)") (class "Default")
      (node (ref "X1") (pin "2") (pinfunction "2_2") (pintype "passive+no_connect"))
    )
    (net (code "27") (name "unconnected-(X1-Pad3)") (class "Default")
      (node (ref "X1") (pin "3") (pinfunction "3_3") (pintype "passive+no_connect"))
    )
    (net (code "28") (name "unconnected-(X1-Pad4)") (class "Default")
      (node (ref "X1") (pin "4") (pinfunction "4_4") (pintype "passive+no_connect"))
    )
    (net (code "29") (name "unconnected-(X1-Pad5)") (class "Default")
      (node (ref "X1") (pin "5") (pinfunction "5_5") (pintype "passive+no_connect"))
    )
    (net (code "30") (name "unconnected-(X1-Pad6)") (class "Default")
      (node (ref "X1") (pin "6") (pinfunction "6_6") (pintype "passive+no_connect"))
    )
    (net (code "31") (name "unconnected-(X1-Pad7)") (class "Default")
      (node (ref "X1") (pin "7") (pinfunction "7_7") (pintype "passive+no_connect"))
    )
    (net (code "32") (name "unconnected-(X1-Pad8)") (class "Default")
      (node (ref "X1") (pin "8") (pinfunction "8_8") (pintype "passive+no_connect"))
    )
    (net (code "33") (name "unconnected-(X4-Pad1)") (class "Default")
      (node (ref "X4") (pin "1") (pinfunction "1_1") (pintype "passive+no_connect"))
    )
    (net (code "34") (name "unconnected-(X4-Pad2)") (class "Default")
      (node (ref "X4") (pin "2") (pinfunction "2_2") (pintype "passive+no_connect"))
    )
    (net (code "35") (name "unconnected-(X4-Pad3)") (class "Default")
      (node (ref "X4") (pin "3") (pinfunction "3_3") (pintype "passive+no_connect"))
    )
    (net (code "36") (name "unconnected-(X4-Pad4)") (class "Default")
      (node (ref "X4") (pin "4") (pinfunction "4_4") (pintype "passive+no_connect"))
    )
    (net (code "37") (name "unconnected-(X4-Pad5)") (class "Default")
      (node (ref "X4") (pin "5") (pinfunction "5_5") (pintype "passive+no_connect"))
    )
    (net (code "38") (name "unconnected-(X4-Pad6)") (class "Default")
      (node (ref "X4") (pin "6") (pinfunction "6_6") (pintype "passive+no_connect"))
    )
    (net (code "39") (name "unconnected-(X4-Pad7)") (class "Default")
      (node (ref "X4") (pin "7") (pinfunction "7_7") (pintype "passive+no_connect"))
    )
    (net (code "40") (name "unconnected-(X4-Pad8)") (class "Default")
      (node (ref "X4") (pin "8") (pinfunction "8_8") (pintype "passive+no_connect"))
    )
  )
)
